# 5V-REG.net
KiCad netlist of a schematic drawn in Altium Designer
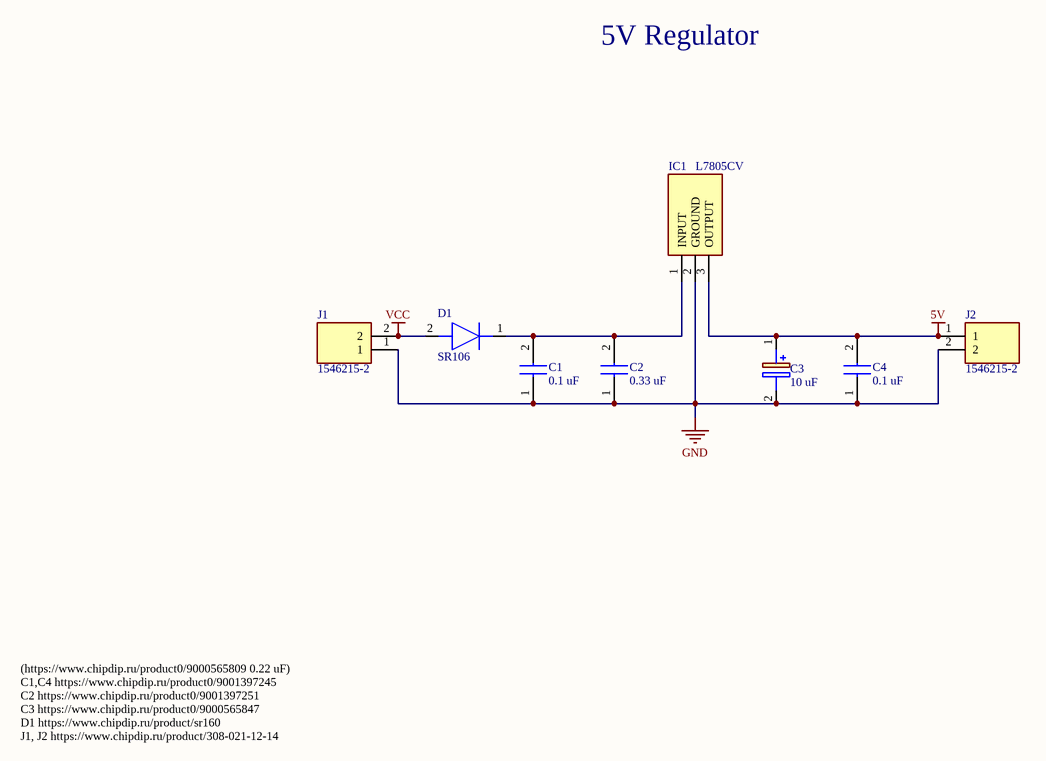
[diagram p0: 5V-REG.SchDoc]

(export (version "E")
  (design (tool "Eeschema 10.0.6"))
  (components
    (comp (ref "C1")
      (value "0.1 uF")
      (footprint "MyLib:C323C104J5R5TA")
      (description "Capacitor")
      (fields
        (field (name "MANUFACTURER_PART_NUMBER") "C323C104J5R5TA")
        (field (name "MOUSER PART NUMBER") "80-C323C104J5R")
      )
      (libsource (lib "MyLib") (part "C323C104J5R5TA"))
    )
    (comp (ref "C2")
      (value "0.33 uF")
      (footprint "MyLib:C323C104J5R5TA")
      (description "Capacitor")
      (fields
        (field (name "MANUFACTURER_PART_NUMBER") "C323C104J5R5TA")
        (field (name "MOUSER PART NUMBER") "80-C323C104J5R")
      )
      (libsource (lib "MyLib") (part "C323C104J5R5TA"))
    )
    (comp (ref "C3")
      (value "10 uF")
      (footprint "SamacSys:CAPPRD200W50D525H1250")
      (description "Capacitor Polarised")
      (fields
        (field (name "MANUFACTURER_PART_NUMBER") "35ZLR56MEFC5X11")
        (field (name "MOUSER PART NUMBER") "232-35ZLR56MEFC5X11")
      )
      (libsource (lib "*") (part "35ZLR56MEFC5X11"))
    )
    (comp (ref "C4")
      (value "0.1 uF")
      (footprint "MyLib:C323C104J5R5TA")
      (description "Capacitor")
      (fields
        (field (name "MANUFACTURER_PART_NUMBER") "C323C104J5R5TA")
        (field (name "MOUSER PART NUMBER") "80-C323C104J5R")
      )
      (libsource (lib "MyLib") (part "C323C104J5R5TA"))
    )
    (comp (ref "D1")
      (value "SR106")
      (footprint "SamacSys:DIOAD1408W86L464D236")
      (description "Diode")
      (fields
        (field (name "MANUFACTURER_PART_NUMBER") "1N5817-T")
        (field (name "MOUSER PART NUMBER") "621-1N5817")
      )
      (libsource (lib "*") (part "1N5817-T"))
    )
    (comp (ref "IC1")
      (value "L7805CV")
      (footprint "SamacSys:TO255P460X1020X2008-3P")
      (description "Integrated Circuit")
      (fields (field (name "MOUSER PART NUMBER") "511-L7805CV"))
      (libsource (lib "*") (part "L7805CV"))
    )
    (comp (ref "J1")
      (value "1546215-2")
      (footprint "SamacSys:15462152")
      (description "Connector")
      (fields (field (name "MOUSER PART NUMBER") "571-1546215-2"))
      (libsource (lib "") (part "1546215-2_1"))
    )
    (comp (ref "J2")
      (value "1546215-2")
      (footprint "SamacSys:15462152")
      (description "Connector")
      (fields (field (name "MOUSER PART NUMBER") "571-1546215-2"))
      (libsource (lib "*") (part "1546215-2"))
    )
  )
  (nets
    (net (code "1") (name "5V") (class "Default")
      (node (ref "C3") (pin "1") (pinfunction "+_1") (pintype "passive"))
      (node (ref "C4") (pin "2") (pinfunction "2_2") (pintype "passive"))
      (node (ref "IC1") (pin "3") (pinfunction "OUTPUT_3") (pintype "passive"))
      (node (ref "J2") (pin "1") (pinfunction "1_1") (pintype "passive"))
    )
    (net (code "2") (name "GND") (class "Default")
      (node (ref "C1") (pin "1") (pinfunction "1_1") (pintype "passive"))
      (node (ref "C2") (pin "1") (pinfunction "1_1") (pintype "passive"))
      (node (ref "C3") (pin "2") (pinfunction "-_2") (pintype "passive"))
      (node (ref "C4") (pin "1") (pinfunction "1_1") (pintype "passive"))
      (node (ref "IC1") (pin "2") (pinfunction "GROUND_2") (pintype "passive"))
      (node (ref "J1") (pin "1") (pinfunction "1_1") (pintype "passive"))
      (node (ref "J2") (pin "2") (pinfunction "2_2") (pintype "passive"))
    )
    (net (code "3") (name "Net-(D1-K)") (class "Default")
      (node (ref "C1") (pin "2") (pinfunction "2_2") (pintype "passive"))
      (node (ref "C2") (pin "2") (pinfunction "2_2") (pintype "passive"))
      (node (ref "D1") (pin "1") (pinfunction "K_1") (pintype "passive"))
      (node (ref "IC1") (pin "1") (pinfunction "INPUT_1") (pintype "passive"))
    )
    (net (code "4") (name "VCC") (class "Default")
      (node (ref "D1") (pin "2") (pinfunction "A_2") (pintype "passive"))
      (node (ref "J1") (pin "2") (pinfunction "2_2") (pintype "passive"))
    )
  )
)
